# SwiftV1.net
KiCad netlist of a schematic drawn in EAGLE
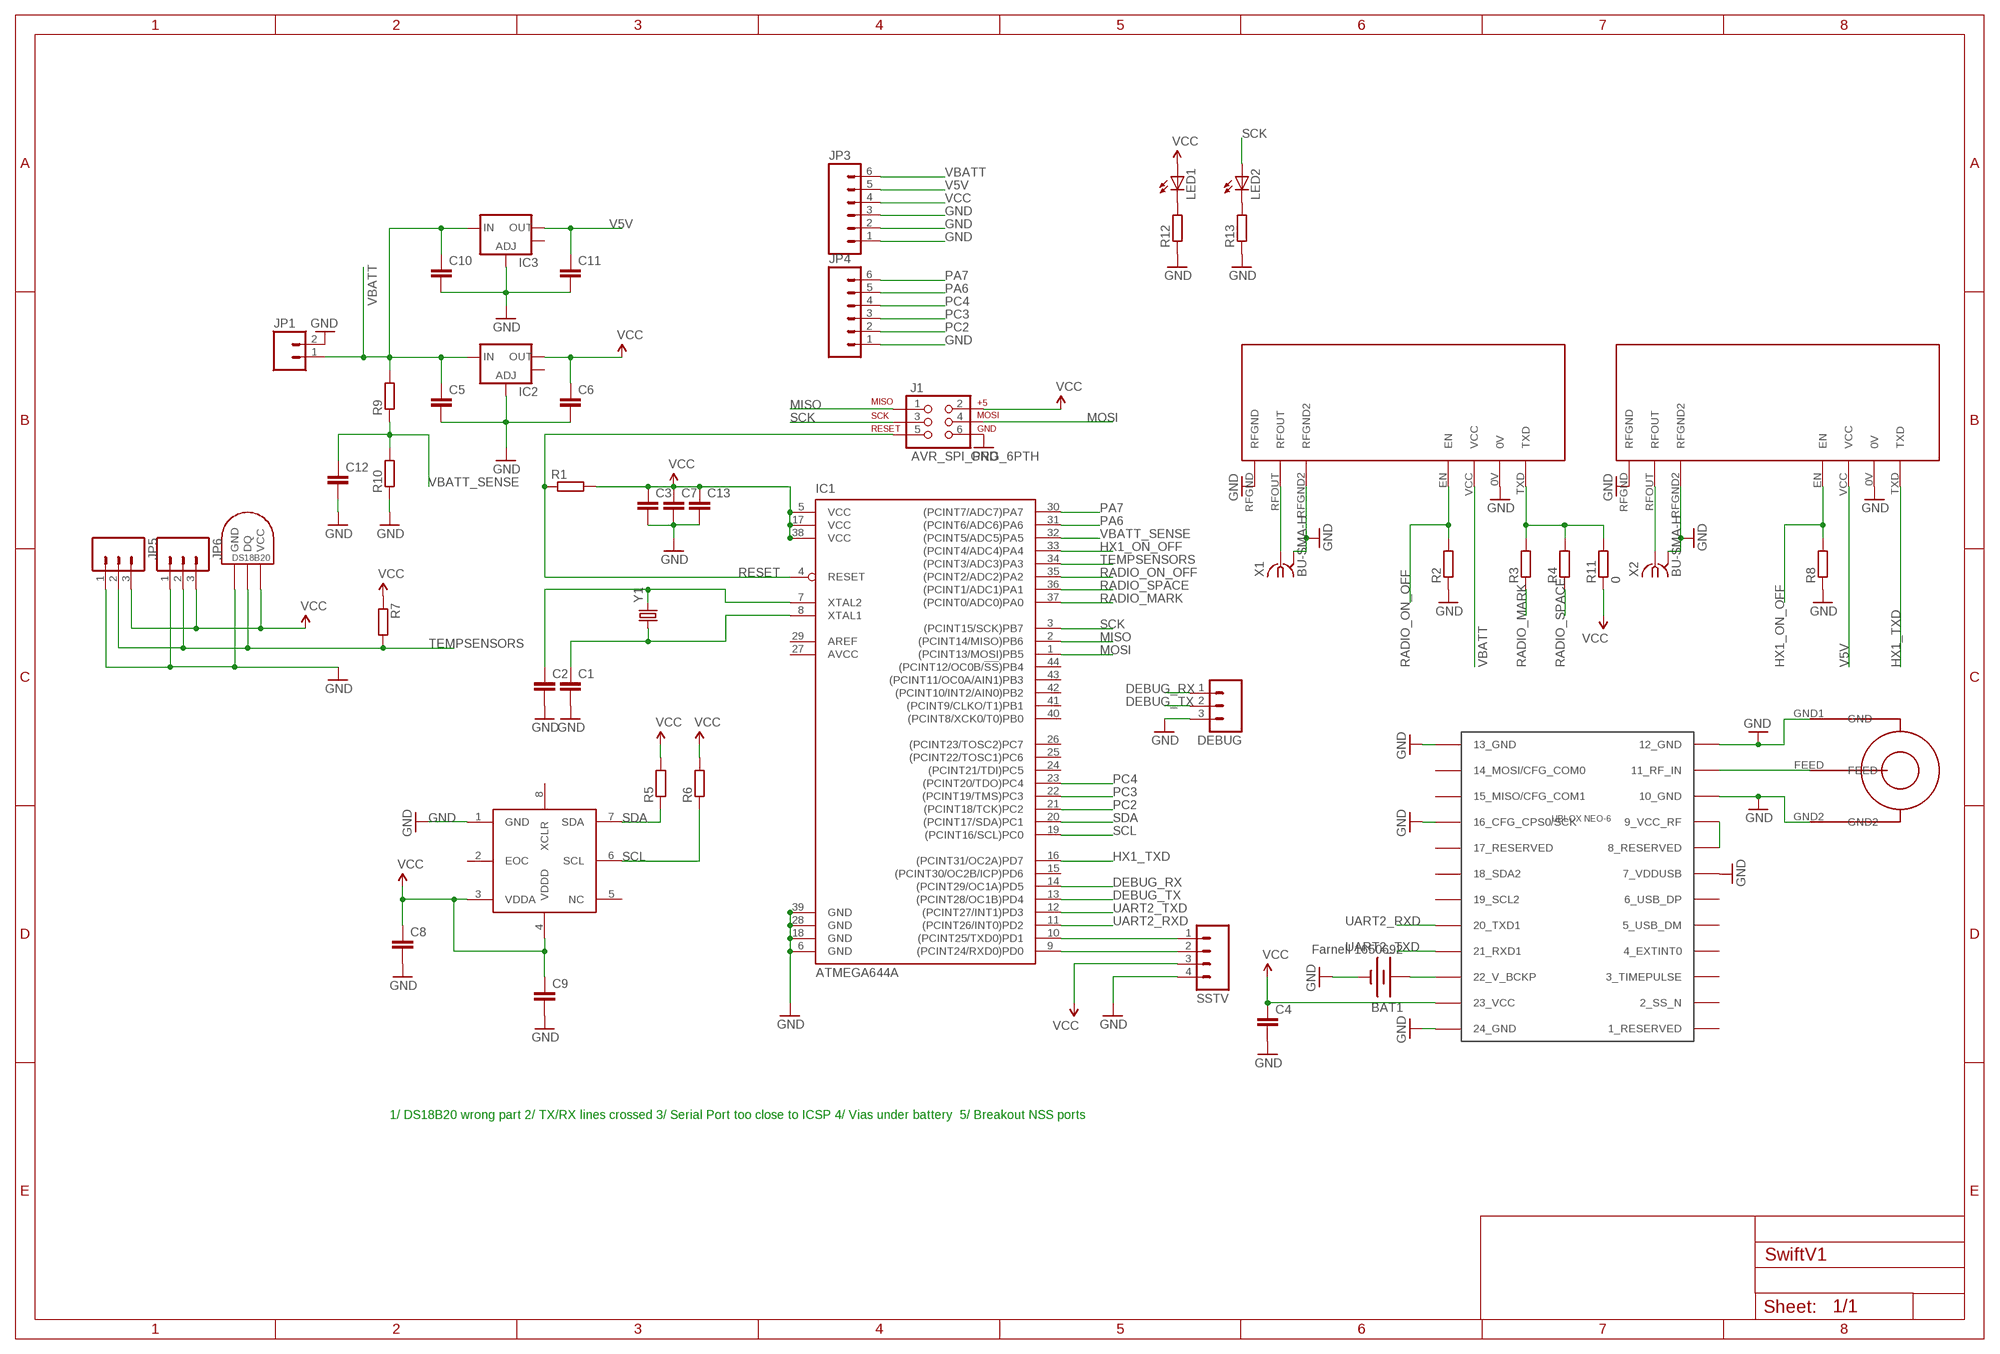
[diagram p0: schematic, sheet 1]

(export (version "E")
  (design (tool "Eeschema 10.0.6"))
  (components
    (comp (ref "BAT1")
      (value "Farnell 1650692")
      (footprint "eagle-import:BATTCON_12MM")
      (libsource (lib "eagle-import") (part "BATTERY12MM"))
    )
    (comp (ref "C1")
      (value "C-EUC0805")
      (footprint "eagle-import:C0805")
      (libsource (lib "eagle-import") (part "C-EUC0805"))
    )
    (comp (ref "C2")
      (value "C-EUC0805")
      (footprint "eagle-import:C0805")
      (libsource (lib "eagle-import") (part "C-EUC0805"))
    )
    (comp (ref "C3")
      (value "C-EUC0805")
      (footprint "eagle-import:C0805")
      (libsource (lib "eagle-import") (part "C-EUC0805"))
    )
    (comp (ref "C4")
      (value "C-EUC0805")
      (footprint "eagle-import:C0805")
      (libsource (lib "eagle-import") (part "C-EUC0805"))
    )
    (comp (ref "C5")
      (value "C-EUC0805")
      (footprint "eagle-import:C0805")
      (libsource (lib "eagle-import") (part "C-EUC0805"))
    )
    (comp (ref "C6")
      (value "C-EUC0805")
      (footprint "eagle-import:C0805")
      (libsource (lib "eagle-import") (part "C-EUC0805"))
    )
    (comp (ref "C7")
      (value "C-EUC0805")
      (footprint "eagle-import:C0805")
      (libsource (lib "eagle-import") (part "C-EUC0805"))
    )
    (comp (ref "C8")
      (value "C-EUC0805")
      (footprint "eagle-import:C0805")
      (libsource (lib "eagle-import") (part "C-EUC0805"))
    )
    (comp (ref "C9")
      (value "C-EUC0805")
      (footprint "eagle-import:C0805")
      (libsource (lib "eagle-import") (part "C-EUC0805"))
    )
    (comp (ref "C10")
      (value "C-EUC0805")
      (footprint "eagle-import:C0805")
      (libsource (lib "eagle-import") (part "C-EUC0805"))
    )
    (comp (ref "C11")
      (value "C-EUC0805")
      (footprint "eagle-import:C0805")
      (libsource (lib "eagle-import") (part "C-EUC0805"))
    )
    (comp (ref "C12")
      (value "C-EUC0805")
      (footprint "eagle-import:C0805")
      (libsource (lib "eagle-import") (part "C-EUC0805"))
    )
    (comp (ref "C13")
      (value "C-EUC0805")
      (footprint "eagle-import:C0805")
      (libsource (lib "eagle-import") (part "C-EUC0805"))
    )
    (comp (ref "DEBUG")
      (value "M03PTH")
      (footprint "eagle-import:1X03")
      (libsource (lib "eagle-import") (part "M03PTH"))
    )
    (comp (ref "IC1")
      (value "ATMEGA644A")
      (footprint "eagle-import:TQFP44")
      (fields (field (name "MPN") "ATMEGA644PV-10AU"))
      (libsource (lib "eagle-import") (part "ATMEGA644A"))
    )
    (comp (ref "IC2")
      (value "V_REG_LM1117SOT223")
      (footprint "eagle-import:SOT223")
      (libsource (lib "eagle-import") (part "V_REG_LM1117SOT223"))
    )
    (comp (ref "IC3")
      (value "V_REG_LM1117SOT223")
      (footprint "eagle-import:SOT223")
      (libsource (lib "eagle-import") (part "V_REG_LM1117SOT223"))
    )
    (comp (ref "J1")
      (value "AVR_SPI_PRG_6PTH")
      (footprint "eagle-import:2X3")
      (libsource (lib "eagle-import") (part "AVR_SPI_PRG_6PTH"))
    )
    (comp (ref "JP1")
      (value "M02JST-PTH-2")
      (footprint "eagle-import:JST-2-PTH")
      (libsource (lib "eagle-import") (part "M02JST-PTH-2"))
    )
    (comp (ref "JP3")
      (value "M06SIP")
      (footprint "eagle-import:1X06")
      (libsource (lib "eagle-import") (part "M06SIP"))
    )
    (comp (ref "JP4")
      (value "M06SIP")
      (footprint "eagle-import:1X06")
      (libsource (lib "eagle-import") (part "M06SIP"))
    )
    (comp (ref "JP5")
      (value "M03JST-PTH")
      (footprint "eagle-import:JST-3-PTH")
      (libsource (lib "eagle-import") (part "M03JST-PTH"))
    )
    (comp (ref "JP6")
      (value "M03JST-PTH")
      (footprint "eagle-import:JST-3-PTH")
      (libsource (lib "eagle-import") (part "M03JST-PTH"))
    )
    (comp (ref "LED1")
      (value "LED0603")
      (footprint "eagle-import:LED-0603")
      (libsource (lib "eagle-import") (part "LED0603"))
    )
    (comp (ref "LED2")
      (value "LED0603")
      (footprint "eagle-import:LED-0603")
      (libsource (lib "eagle-import") (part "LED0603"))
    )
    (comp (ref "R1")
      (value "R-EU_R0805")
      (footprint "eagle-import:R0805")
      (libsource (lib "eagle-import") (part "R-EU_R0805"))
    )
    (comp (ref "R2")
      (value "R-EU_R0805")
      (footprint "eagle-import:R0805")
      (libsource (lib "eagle-import") (part "R-EU_R0805"))
    )
    (comp (ref "R3")
      (value "R-EU_R0805")
      (footprint "eagle-import:R0805")
      (libsource (lib "eagle-import") (part "R-EU_R0805"))
    )
    (comp (ref "R4")
      (value "R-EU_R0805")
      (footprint "eagle-import:R0805")
      (libsource (lib "eagle-import") (part "R-EU_R0805"))
    )
    (comp (ref "R5")
      (value "R-EU_R0805")
      (footprint "eagle-import:R0805")
      (libsource (lib "eagle-import") (part "R-EU_R0805"))
    )
    (comp (ref "R6")
      (value "R-EU_R0805")
      (footprint "eagle-import:R0805")
      (libsource (lib "eagle-import") (part "R-EU_R0805"))
    )
    (comp (ref "R7")
      (value "R-EU_R0805")
      (footprint "eagle-import:R0805")
      (libsource (lib "eagle-import") (part "R-EU_R0805"))
    )
    (comp (ref "R8")
      (value "R-EU_R0805")
      (footprint "eagle-import:R0805")
      (libsource (lib "eagle-import") (part "R-EU_R0805"))
    )
    (comp (ref "R9")
      (value "R-EU_R0805")
      (footprint "eagle-import:R0805")
      (libsource (lib "eagle-import") (part "R-EU_R0805"))
    )
    (comp (ref "R10")
      (value "R-EU_R0805")
      (footprint "eagle-import:R0805")
      (libsource (lib "eagle-import") (part "R-EU_R0805"))
    )
    (comp (ref "R11")
      (value "0")
      (footprint "eagle-import:R0805")
      (libsource (lib "eagle-import") (part "R-EU_R0805"))
    )
    (comp (ref "R12")
      (value "R-EU_R0805")
      (footprint "eagle-import:R0805")
      (libsource (lib "eagle-import") (part "R-EU_R0805"))
    )
    (comp (ref "R13")
      (value "R-EU_R0805")
      (footprint "eagle-import:R0805")
      (libsource (lib "eagle-import") (part "R-EU_R0805"))
    )
    (comp (ref "SSTV")
      (value "M04PTH")
      (footprint "eagle-import:1X04")
      (libsource (lib "eagle-import") (part "M04PTH"))
    )
    (comp (ref "TEMPINT")
      (value "DS1821")
      (footprint "eagle-import:DS18B20_SOIC")
      (libsource (lib "eagle-import") (part "DS1820SOIC"))
    )
    (comp (ref "U$1")
      (value "BMP085")
      (footprint "eagle-import:BMP085")
      (libsource (lib "eagle-import") (part "BMP085"))
    )
    (comp (ref "U$2")
      (value "NTX2")
      (footprint "eagle-import:NTX2")
      (libsource (lib "eagle-import") (part "NTX2"))
    )
    (comp (ref "U$3")
      (value "SARANTEL-SR1202")
      (footprint "eagle-import:SARANTEL-SR1202")
      (libsource (lib "eagle-import") (part "SARANTEL-SR1202"))
    )
    (comp (ref "U$4")
      (value "UBLOX_NEO-6")
      (footprint "eagle-import:UBLOX_NEO-6P")
      (libsource (lib "eagle-import") (part "UBLOX_NEO-6"))
    )
    (comp (ref "U$5")
      (value "NTX2")
      (footprint "eagle-import:NTX2")
      (libsource (lib "eagle-import") (part "NTX2"))
    )
    (comp (ref "X1")
      (value "BU-SMA-H")
      (footprint "eagle-import:BU-SMA-H")
      (libsource (lib "eagle-import") (part "BU-SMA-H"))
    )
    (comp (ref "X2")
      (value "BU-SMA-H")
      (footprint "eagle-import:BU-SMA-H")
      (libsource (lib "eagle-import") (part "BU-SMA-H"))
    )
    (comp (ref "Y1")
      (value "CRYSTALSMD")
      (footprint "eagle-import:HC49UP")
      (libsource (lib "eagle-import") (part "CRYSTALSMD"))
    )
  )
  (nets
    (net (code "1") (name "/AVCC") (class "Default")
      (node (ref "IC1") (pin "27") (pinfunction "AVCC_27") (pintype "power_in"))
    )
    (net (code "2") (name "/DEBUG_RX") (class "Default")
      (node (ref "DEBUG") (pin "1") (pinfunction "1_1") (pintype "passive"))
      (node (ref "IC1") (pin "14") (pinfunction "(PCINT29/OC1A)PD5_14") (pintype "bidirectional"))
    )
    (net (code "3") (name "/DEBUG_TX") (class "Default")
      (node (ref "DEBUG") (pin "2") (pinfunction "2_2") (pintype "passive"))
      (node (ref "IC1") (pin "13") (pinfunction "(PCINT28/OC1B)PD4_13") (pintype "bidirectional"))
    )
    (net (code "4") (name "/HX1_ON_OFF") (class "Default")
      (node (ref "IC1") (pin "33") (pinfunction "(PCINT4/ADC4)PA4_33") (pintype "bidirectional"))
      (node (ref "R8") (pin "2") (pinfunction "2_2") (pintype "passive"))
      (node (ref "U$5") (pin "EN") (pinfunction "EN_EN") (pintype "bidirectional"))
    )
    (net (code "5") (name "/HX1_TXD") (class "Default")
      (node (ref "IC1") (pin "16") (pinfunction "(PCINT31/OC2A)PD7_16") (pintype "bidirectional"))
      (node (ref "U$5") (pin "TXD") (pinfunction "TXD_TXD") (pintype "bidirectional"))
    )
    (net (code "6") (name "/MISO") (class "Default")
      (node (ref "IC1") (pin "2") (pinfunction "(PCINT14/MISO)PB6_2") (pintype "bidirectional"))
      (node (ref "J1") (pin "1") (pinfunction "1_1") (pintype "passive"))
    )
    (net (code "7") (name "/MOSI") (class "Default")
      (node (ref "IC1") (pin "1") (pinfunction "(PCINT13/MOSI)PB5_1") (pintype "bidirectional"))
      (node (ref "J1") (pin "4") (pinfunction "4_4") (pintype "passive"))
    )
    (net (code "8") (name "/PA6") (class "Default")
      (node (ref "IC1") (pin "31") (pinfunction "(PCINT6/ADC6)PA6_31") (pintype "bidirectional"))
      (node (ref "JP4") (pin "5") (pinfunction "5_5") (pintype "passive"))
    )
    (net (code "9") (name "/PA7") (class "Default")
      (node (ref "IC1") (pin "30") (pinfunction "(PCINT7/ADC7)PA7_30") (pintype "bidirectional"))
      (node (ref "JP4") (pin "6") (pinfunction "6_6") (pintype "passive"))
    )
    (net (code "10") (name "/PC2") (class "Default")
      (node (ref "IC1") (pin "21") (pinfunction "(PCINT18/TCK)PC2_21") (pintype "output"))
      (node (ref "JP4") (pin "2") (pinfunction "2_2") (pintype "passive"))
    )
    (net (code "11") (name "/PC3") (class "Default")
      (node (ref "IC1") (pin "22") (pinfunction "(PCINT19/TMS)PC3_22") (pintype "output"))
      (node (ref "JP4") (pin "3") (pinfunction "3_3") (pintype "passive"))
    )
    (net (code "12") (name "/PC4") (class "Default")
      (node (ref "IC1") (pin "23") (pinfunction "(PCINT20/TDO)PC4_23") (pintype "output"))
      (node (ref "JP4") (pin "4") (pinfunction "4_4") (pintype "passive"))
    )
    (net (code "13") (name "/RADIO_MARK") (class "Default")
      (node (ref "IC1") (pin "37") (pinfunction "(PCINT0/ADC0)PA0_37") (pintype "bidirectional"))
      (node (ref "R3") (pin "1") (pinfunction "1_1") (pintype "passive"))
    )
    (net (code "14") (name "/RADIO_ON_OFF") (class "Default")
      (node (ref "IC1") (pin "35") (pinfunction "(PCINT2/ADC2)PA2_35") (pintype "bidirectional"))
      (node (ref "R2") (pin "2") (pinfunction "2_2") (pintype "passive"))
      (node (ref "U$2") (pin "EN") (pinfunction "EN_EN") (pintype "bidirectional"))
    )
    (net (code "15") (name "/RADIO_SPACE") (class "Default")
      (node (ref "IC1") (pin "36") (pinfunction "(PCINT1/ADC1)PA1_36") (pintype "bidirectional"))
      (node (ref "R4") (pin "1") (pinfunction "1_1") (pintype "passive"))
    )
    (net (code "16") (name "/RESET") (class "Default")
      (node (ref "IC1") (pin "4") (pinfunction "RESET_4") (pintype "input"))
      (node (ref "J1") (pin "5") (pinfunction "5_5") (pintype "passive"))
      (node (ref "R1") (pin "1") (pinfunction "1_1") (pintype "passive"))
    )
    (net (code "17") (name "/SCK") (class "Default")
      (node (ref "IC1") (pin "3") (pinfunction "(PCINT15/SCK)PB7_3") (pintype "bidirectional"))
      (node (ref "J1") (pin "3") (pinfunction "3_3") (pintype "passive"))
      (node (ref "LED2") (pin "A") (pinfunction "A_A") (pintype "passive"))
    )
    (net (code "18") (name "/SCL") (class "Default")
      (node (ref "IC1") (pin "19") (pinfunction "(PCINT16/SCL)PC0_19") (pintype "output"))
      (node (ref "R6") (pin "1") (pinfunction "1_1") (pintype "passive"))
      (node (ref "U$1") (pin "6") (pinfunction "SCL_6") (pintype "bidirectional"))
    )
    (net (code "19") (name "/SDA") (class "Default")
      (node (ref "IC1") (pin "20") (pinfunction "(PCINT17/SDA)PC1_20") (pintype "output"))
      (node (ref "R5") (pin "1") (pinfunction "1_1") (pintype "passive"))
      (node (ref "U$1") (pin "7") (pinfunction "SDA_7") (pintype "bidirectional"))
    )
    (net (code "20") (name "/TEMPSENSORS") (class "Default")
      (node (ref "IC1") (pin "34") (pinfunction "(PCINT3/ADC3)PA3_34") (pintype "bidirectional"))
      (node (ref "JP5") (pin "2") (pinfunction "2_2") (pintype "passive"))
      (node (ref "JP6") (pin "2") (pinfunction "2_2") (pintype "passive"))
      (node (ref "R7") (pin "2") (pinfunction "2_2") (pintype "passive"))
      (node (ref "TEMPINT") (pin "DQ") (pinfunction "DQ_DQ") (pintype "bidirectional"))
    )
    (net (code "21") (name "/UART2_RXD") (class "Default")
      (node (ref "IC1") (pin "11") (pinfunction "(PCINT26/INT0)PD2_11") (pintype "bidirectional"))
      (node (ref "U$4") (pin "20_TXD1") (pinfunction "20_TXD1_20_TXD1") (pintype "bidirectional"))
    )
    (net (code "22") (name "/UART2_TXD") (class "Default")
      (node (ref "IC1") (pin "12") (pinfunction "(PCINT27/INT1)PD3_12") (pintype "bidirectional"))
      (node (ref "U$4") (pin "21_RXD1") (pinfunction "21_RXD1_21_RXD1") (pintype "bidirectional"))
    )
    (net (code "23") (name "/V5V") (class "Default")
      (node (ref "C11") (pin "1") (pinfunction "1_1") (pintype "passive"))
      (node (ref "IC3") (pin "2") (pinfunction "OUT_2") (pintype "output"))
      (node (ref "JP3") (pin "5") (pinfunction "5_5") (pintype "passive"))
      (node (ref "U$5") (pin "VCC") (pinfunction "VCC_VCC") (pintype "bidirectional"))
    )
    (net (code "24") (name "/VBATT") (class "Default")
      (node (ref "C10") (pin "1") (pinfunction "1_1") (pintype "passive"))
      (node (ref "C5") (pin "1") (pinfunction "1_1") (pintype "passive"))
      (node (ref "IC2") (pin "3") (pinfunction "IN_3") (pintype "input"))
      (node (ref "IC3") (pin "3") (pinfunction "IN_3") (pintype "input"))
      (node (ref "JP1") (pin "1") (pinfunction "1_1") (pintype "passive"))
      (node (ref "JP3") (pin "6") (pinfunction "6_6") (pintype "passive"))
      (node (ref "R9") (pin "2") (pinfunction "2_2") (pintype "passive"))
      (node (ref "U$2") (pin "VCC") (pinfunction "VCC_VCC") (pintype "bidirectional"))
    )
    (net (code "25") (name "/VBATT_SENSE") (class "Default")
      (node (ref "C12") (pin "1") (pinfunction "1_1") (pintype "passive"))
      (node (ref "IC1") (pin "32") (pinfunction "(PCINT5/ADC5)PA5_32") (pintype "bidirectional"))
      (node (ref "R10") (pin "2") (pinfunction "2_2") (pintype "passive"))
      (node (ref "R9") (pin "1") (pinfunction "1_1") (pintype "passive"))
    )
    (net (code "26") (name "GND") (class "Default")
      (node (ref "BAT1") (pin "GND") (pinfunction "-_GND") (pintype "power_in"))
      (node (ref "C1") (pin "2") (pinfunction "2_2") (pintype "passive"))
      (node (ref "C10") (pin "2") (pinfunction "2_2") (pintype "passive"))
      (node (ref "C11") (pin "2") (pinfunction "2_2") (pintype "passive"))
      (node (ref "C12") (pin "2") (pinfunction "2_2") (pintype "passive"))
      (node (ref "C13") (pin "2") (pinfunction "2_2") (pintype "passive"))
      (node (ref "C2") (pin "2") (pinfunction "2_2") (pintype "passive"))
      (node (ref "C3") (pin "2") (pinfunction "2_2") (pintype "passive"))
      (node (ref "C4") (pin "2") (pinfunction "2_2") (pintype "passive"))
      (node (ref "C5") (pin "2") (pinfunction "2_2") (pintype "passive"))
      (node (ref "C6") (pin "2") (pinfunction "2_2") (pintype "passive"))
      (node (ref "C7") (pin "2") (pinfunction "2_2") (pintype "passive"))
      (node (ref "C8") (pin "2") (pinfunction "2_2") (pintype "passive"))
      (node (ref "C9") (pin "2") (pinfunction "2_2") (pintype "passive"))
      (node (ref "DEBUG") (pin "3") (pinfunction "3_3") (pintype "passive"))
      (node (ref "IC1") (pin "18") (pinfunction "GND_18") (pintype "power_in"))
      (node (ref "IC1") (pin "28") (pinfunction "GND_28") (pintype "power_in"))
      (node (ref "IC1") (pin "39") (pinfunction "GND_39") (pintype "power_in"))
      (node (ref "IC1") (pin "6") (pinfunction "GND_6") (pintype "power_in"))
      (node (ref "IC2") (pin "1") (pinfunction "ADJ_1") (pintype "input"))
      (node (ref "IC3") (pin "1") (pinfunction "ADJ_1") (pintype "input"))
      (node (ref "J1") (pin "6") (pinfunction "6_6") (pintype "passive"))
      (node (ref "JP1") (pin "2") (pinfunction "2_2") (pintype "passive"))
      (node (ref "JP3") (pin "1") (pinfunction "1_1") (pintype "passive"))
      (node (ref "JP3") (pin "2") (pinfunction "2_2") (pintype "passive"))
      (node (ref "JP3") (pin "3") (pinfunction "3_3") (pintype "passive"))
      (node (ref "JP4") (pin "1") (pinfunction "1_1") (pintype "passive"))
      (node (ref "JP5") (pin "1") (pinfunction "1_1") (pintype "passive"))
      (node (ref "JP6") (pin "1") (pinfunction "1_1") (pintype "passive"))
      (node (ref "R10") (pin "1") (pinfunction "1_1") (pintype "passive"))
      (node (ref "R12") (pin "1") (pinfunction "1_1") (pintype "passive"))
      (node (ref "R13") (pin "1") (pinfunction "1_1") (pintype "passive"))
      (node (ref "R2") (pin "1") (pinfunction "1_1") (pintype "passive"))
      (node (ref "R8") (pin "1") (pinfunction "1_1") (pintype "passive"))
      (node (ref "SSTV") (pin "4") (pinfunction "4_4") (pintype "passive"))
      (node (ref "TEMPINT") (pin "GND") (pinfunction "GND_GND") (pintype "power_in"))
      (node (ref "U$1") (pin "1") (pinfunction "GND_1") (pintype "bidirectional"))
      (node (ref "U$2") (pin "0V") (pinfunction "0V_0V") (pintype "bidirectional"))
      (node (ref "U$2") (pin "RFGND") (pinfunction "RFGND_RFGND") (pintype "bidirectional"))
      (node (ref "U$2") (pin "RFGND2") (pinfunction "RFGND2_RFGND2") (pintype "bidirectional"))
      (node (ref "U$3") (pin "GND1") (pinfunction "GND_GND1") (pintype "bidirectional"))
      (node (ref "U$3") (pin "GND2") (pinfunction "GND2_GND2") (pintype "bidirectional"))
      (node (ref "U$4") (pin "10_GND") (pinfunction "10_GND_10_GND") (pintype "bidirectional"))
      (node (ref "U$4") (pin "12_GND") (pinfunction "12_GND_12_GND") (pintype "bidirectional"))
      (node (ref "U$4") (pin "13_GND") (pinfunction "13_GND_13_GND") (pintype "bidirectional"))
      (node (ref "U$4") (pin "16_CFG_CPS0/SCK") (pinfunction "16_CFG_CPS0/SCK_16_CFG_CPS0/SCK") (pintype "bidirectional"))
      (node (ref "U$4") (pin "24_GND") (pinfunction "24_GND_24_GND") (pintype "bidirectional"))
      (node (ref "U$4") (pin "7_VDDUSB") (pinfunction "7_VDDUSB_7_VDDUSB") (pintype "bidirectional"))
      (node (ref "U$5") (pin "0V") (pinfunction "0V_0V") (pintype "bidirectional"))
      (node (ref "U$5") (pin "RFGND") (pinfunction "RFGND_RFGND") (pintype "bidirectional"))
      (node (ref "U$5") (pin "RFGND2") (pinfunction "RFGND2_RFGND2") (pintype "bidirectional"))
      (node (ref "X1") (pin "2") (pinfunction "GND_2") (pintype "power_in"))
      (node (ref "X2") (pin "2") (pinfunction "GND_2") (pintype "power_in"))
    )
    (net (code "27") (name "Net-(BAT1-+)") (class "Default")
      (node (ref "BAT1") (pin "PWR@1") (pinfunction "+_PWR@1") (pintype "power_in"))
      (node (ref "U$4") (pin "22_V_BCKP") (pinfunction "22_V_BCKP_22_V_BCKP") (pintype "bidirectional"))
    )
    (net (code "28") (name "Net-(IC1-(PCINT24{slash}RXD0)PD0)") (class "Default")
      (node (ref "IC1") (pin "9") (pinfunction "(PCINT24/RXD0)PD0_9") (pintype "bidirectional"))
      (node (ref "SSTV") (pin "2") (pinfunction "2_2") (pintype "passive"))
    )
    (net (code "29") (name "Net-(IC1-(PCINT25{slash}TXD0)PD1)") (class "Default")
      (node (ref "IC1") (pin "10") (pinfunction "(PCINT25/TXD0)PD1_10") (pintype "bidirectional"))
      (node (ref "SSTV") (pin "1") (pinfunction "1_1") (pintype "passive"))
    )
    (net (code "30") (name "Net-(IC1-XTAL1)") (class "Default")
      (node (ref "C1") (pin "1") (pinfunction "1_1") (pintype "passive"))
      (node (ref "IC1") (pin "8") (pinfunction "XTAL1_8") (pintype "bidirectional"))
      (node (ref "Y1") (pin "1") (pinfunction "1_1") (pintype "passive"))
    )
    (net (code "31") (name "Net-(IC1-XTAL2)") (class "Default")
      (node (ref "C2") (pin "1") (pinfunction "1_1") (pintype "passive"))
      (node (ref "IC1") (pin "7") (pinfunction "XTAL2_7") (pintype "bidirectional"))
      (node (ref "Y1") (pin "2") (pinfunction "2_2") (pintype "passive"))
    )
    (net (code "32") (name "Net-(LED1-PadC)") (class "Default")
      (node (ref "LED1") (pin "C") (pinfunction "C_C") (pintype "passive"))
      (node (ref "R12") (pin "2") (pinfunction "2_2") (pintype "passive"))
    )
    (net (code "33") (name "Net-(LED2-PadC)") (class "Default")
      (node (ref "LED2") (pin "C") (pinfunction "C_C") (pintype "passive"))
      (node (ref "R13") (pin "2") (pinfunction "2_2") (pintype "passive"))
    )
    (net (code "34") (name "Net-(R11-Pad2)") (class "Default")
      (node (ref "R11") (pin "2") (pinfunction "2_2") (pintype "passive"))
      (node (ref "R3") (pin "2") (pinfunction "2_2") (pintype "passive"))
      (node (ref "R4") (pin "2") (pinfunction "2_2") (pintype "passive"))
      (node (ref "U$2") (pin "TXD") (pinfunction "TXD_TXD") (pintype "bidirectional"))
    )
    (net (code "35") (name "Net-(U$2-PadRFOUT)") (class "Default")
      (node (ref "U$2") (pin "RFOUT") (pinfunction "RFOUT_RFOUT") (pintype "bidirectional"))
      (node (ref "X1") (pin "1") (pinfunction "1_1") (pintype "passive"))
    )
    (net (code "36") (name "Net-(U$3-PadFEED)") (class "Default")
      (node (ref "U$3") (pin "FEED") (pinfunction "FEED_FEED") (pintype "bidirectional"))
      (node (ref "U$4") (pin "11_RF_IN") (pinfunction "11_RF_IN_11_RF_IN") (pintype "bidirectional"))
    )
    (net (code "37") (name "Net-(U$4-Pad8_RESERVED)") (class "Default")
      (node (ref "U$4") (pin "8_RESERVED") (pinfunction "8_RESERVED_8_RESERVED") (pintype "bidirectional"))
      (node (ref "U$4") (pin "9_VCC_RF") (pinfunction "9_VCC_RF_9_VCC_RF") (pintype "bidirectional"))
    )
    (net (code "38") (name "Net-(U$5-PadRFOUT)") (class "Default")
      (node (ref "U$5") (pin "RFOUT") (pinfunction "RFOUT_RFOUT") (pintype "bidirectional"))
      (node (ref "X2") (pin "1") (pinfunction "1_1") (pintype "passive"))
    )
    (net (code "39") (name "VCC") (class "Default")
      (node (ref "C13") (pin "1") (pinfunction "1_1") (pintype "passive"))
      (node (ref "C3") (pin "1") (pinfunction "1_1") (pintype "passive"))
      (node (ref "C4") (pin "1") (pinfunction "1_1") (pintype "passive"))
      (node (ref "C6") (pin "1") (pinfunction "1_1") (pintype "passive"))
      (node (ref "C7") (pin "1") (pinfunction "1_1") (pintype "passive"))
      (node (ref "C8") (pin "1") (pinfunction "1_1") (pintype "passive"))
      (node (ref "C9") (pin "1") (pinfunction "1_1") (pintype "passive"))
      (node (ref "IC1") (pin "17") (pinfunction "VCC_17") (pintype "power_in"))
      (node (ref "IC1") (pin "38") (pinfunction "VCC_38") (pintype "power_in"))
      (node (ref "IC1") (pin "5") (pinfunction "VCC_5") (pintype "power_in"))
      (node (ref "IC2") (pin "2") (pinfunction "OUT_2") (pintype "output"))
      (node (ref "J1") (pin "2") (pinfunction "2_2") (pintype "passive"))
      (node (ref "JP3") (pin "4") (pinfunction "4_4") (pintype "passive"))
      (node (ref "JP5") (pin "3") (pinfunction "3_3") (pintype "passive"))
      (node (ref "JP6") (pin "3") (pinfunction "3_3") (pintype "passive"))
      (node (ref "LED1") (pin "A") (pinfunction "A_A") (pintype "passive"))
      (node (ref "R1") (pin "2") (pinfunction "2_2") (pintype "passive"))
      (node (ref "R11") (pin "1") (pinfunction "1_1") (pintype "passive"))
      (node (ref "R5") (pin "2") (pinfunction "2_2") (pintype "passive"))
      (node (ref "R6") (pin "2") (pinfunction "2_2") (pintype "passive"))
      (node (ref "R7") (pin "1") (pinfunction "1_1") (pintype "passive"))
      (node (ref "SSTV") (pin "3") (pinfunction "3_3") (pintype "passive"))
      (node (ref "TEMPINT") (pin "VCC") (pinfunction "VCC_VCC") (pintype "power_in"))
      (node (ref "U$1") (pin "3") (pinfunction "VDDA_3") (pintype "bidirectional"))
      (node (ref "U$1") (pin "4") (pinfunction "VDDD_4") (pintype "bidirectional"))
      (node (ref "U$4") (pin "23_VCC") (pinfunction "23_VCC_23_VCC") (pintype "bidirectional"))
    )
    (net (code "40") (name "unconnected-(IC1-(PCINT8{slash}XCK0{slash}T0)PB0-Pad40)") (class "Default")
      (node (ref "IC1") (pin "40") (pinfunction "(PCINT8/XCK0/T0)PB0_40") (pintype "bidirectional"))
    )
    (net (code "41") (name "unconnected-(IC1-(PCINT9{slash}CLKO{slash}T1)PB1-Pad41)") (class "Default")
      (node (ref "IC1") (pin "41") (pinfunction "(PCINT9/CLKO/T1)PB1_41") (pintype "bidirectional"))
    )
    (net (code "42") (name "unconnected-(IC1-(PCINT10{slash}INT2{slash}AIN0)PB2-Pad42)") (class "Default")
      (node (ref "IC1") (pin "42") (pinfunction "(PCINT10/INT2/AIN0)PB2_42") (pintype "bidirectional"))
    )
    (net (code "43") (name "unconnected-(IC1-(PCINT11{slash}OC0A{slash}AIN1)PB3-Pad43)") (class "Default")
      (node (ref "IC1") (pin "43") (pinfunction "(PCINT11/OC0A/AIN1)PB3_43") (pintype "bidirectional"))
    )
    (net (code "44") (name "unconnected-(IC1-(PCINT12{slash}OC0B{slash}~{SS})PB4-Pad44)") (class "Default")
      (node (ref "IC1") (pin "44") (pinfunction "(PCINT12/OC0B/~{SS})PB4_44") (pintype "bidirectional"))
    )
    (net (code "45") (name "unconnected-(IC1-(PCINT21{slash}TDI)PC5-Pad24)") (class "Default")
      (node (ref "IC1") (pin "24") (pinfunction "(PCINT21/TDI)PC5_24") (pintype "output"))
    )
    (net (code "46") (name "unconnected-(IC1-(PCINT22{slash}TOSC1)PC6-Pad25)") (class "Default")
      (node (ref "IC1") (pin "25") (pinfunction "(PCINT22/TOSC1)PC6_25") (pintype "output"))
    )
    (net (code "47") (name "unconnected-(IC1-(PCINT23{slash}TOSC2)PC7-Pad26)") (class "Default")
      (node (ref "IC1") (pin "26") (pinfunction "(PCINT23/TOSC2)PC7_26") (pintype "output"))
    )
    (net (code "48") (name "unconnected-(IC1-(PCINT30{slash}OC2B{slash}ICP)PD6-Pad15)") (class "Default")
      (node (ref "IC1") (pin "15") (pinfunction "(PCINT30/OC2B/ICP)PD6_15") (pintype "bidirectional"))
    )
    (net (code "49") (name "unconnected-(IC1-AREF-Pad29)") (class "Default")
      (node (ref "IC1") (pin "29") (pinfunction "AREF_29") (pintype "passive"))
    )
    (net (code "50") (name "unconnected-(IC2-OUT-Pad4)") (class "Default")
      (node (ref "IC2") (pin "4") (pinfunction "OUT_4") (pintype "output"))
    )
    (net (code "51") (name "unconnected-(IC3-OUT-Pad4)") (class "Default")
      (node (ref "IC3") (pin "4") (pinfunction "OUT_4") (pintype "output"))
    )
    (net (code "52") (name "unconnected-(U$1-EOC-Pad2)") (class "Default")
      (node (ref "U$1") (pin "2") (pinfunction "EOC_2") (pintype "bidirectional"))
    )
    (net (code "53") (name "unconnected-(U$1-NC-Pad5)") (class "Default")
      (node (ref "U$1") (pin "5") (pinfunction "NC_5") (pintype "bidirectional"))
    )
    (net (code "54") (name "unconnected-(U$1-XCLR-Pad8)") (class "Default")
      (node (ref "U$1") (pin "8") (pinfunction "XCLR_8") (pintype "bidirectional"))
    )
    (net (code "55") (name "unconnected-(U$4-Pad1_RESERVED)") (class "Default")
      (node (ref "U$4") (pin "1_RESERVED") (pinfunction "1_RESERVED_1_RESERVED") (pintype "bidirectional"))
    )
    (net (code "56") (name "unconnected-(U$4-Pad2_SS_N)") (class "Default")
      (node (ref "U$4") (pin "2_SS_N") (pinfunction "2_SS_N_2_SS_N") (pintype "bidirectional"))
    )
    (net (code "57") (name "unconnected-(U$4-Pad3_TIMEPULSE)") (class "Default")
      (node (ref "U$4") (pin "3_TIMEPULSE") (pinfunction "3_TIMEPULSE_3_TIMEPULSE") (pintype "bidirectional"))
    )
    (net (code "58") (name "unconnected-(U$4-Pad4_EXTINT0)") (class "Default")
      (node (ref "U$4") (pin "4_EXTINT0") (pinfunction "4_EXTINT0_4_EXTINT0") (pintype "bidirectional"))
    )
    (net (code "59") (name "unconnected-(U$4-Pad5_USB_DM)") (class "Default")
      (node (ref "U$4") (pin "5_USB_DM") (pinfunction "5_USB_DM_5_USB_DM") (pintype "bidirectional"))
    )
    (net (code "60") (name "unconnected-(U$4-Pad6_USB_DP)") (class "Default")
      (node (ref "U$4") (pin "6_USB_DP") (pinfunction "6_USB_DP_6_USB_DP") (pintype "bidirectional"))
    )
    (net (code "61") (name "unconnected-(U$4-Pad14_MOSI{slash}CFG_COM0)") (class "Default")
      (node (ref "U$4") (pin "14_MOSI/CFG_COM0") (pinfunction "14_MOSI/CFG_COM0_14_MOSI/CFG_COM0") (pintype "bidirectional"))
    )
    (net (code "62") (name "unconnected-(U$4-Pad15_MISO{slash}CFG_COM1)") (class "Default")
      (node (ref "U$4") (pin "15_MISO/CFG_COM1") (pinfunction "15_MISO/CFG_COM1_15_MISO/CFG_COM1") (pintype "bidirectional"))
    )
    (net (code "63") (name "unconnected-(U$4-Pad17_RESERVED)") (class "Default")
      (node (ref "U$4") (pin "17_RESERVED") (pinfunction "17_RESERVED_17_RESERVED") (pintype "bidirectional"))
    )
    (net (code "64") (name "unconnected-(U$4-Pad18_SDA2)") (class "Default")
      (node (ref "U$4") (pin "18_SDA2") (pinfunction "18_SDA2_18_SDA2") (pintype "bidirectional"))
    )
    (net (code "65") (name "unconnected-(U$4-Pad19_SCL2)") (class "Default")
      (node (ref "U$4") (pin "19_SCL2") (pinfunction "19_SCL2_19_SCL2") (pintype "bidirectional"))
    )
  )
)
